# biosense_bgm220-pcbcart-cc-bma-flex-0521.net
KiCad netlist of a schematic drawn in EAGLE
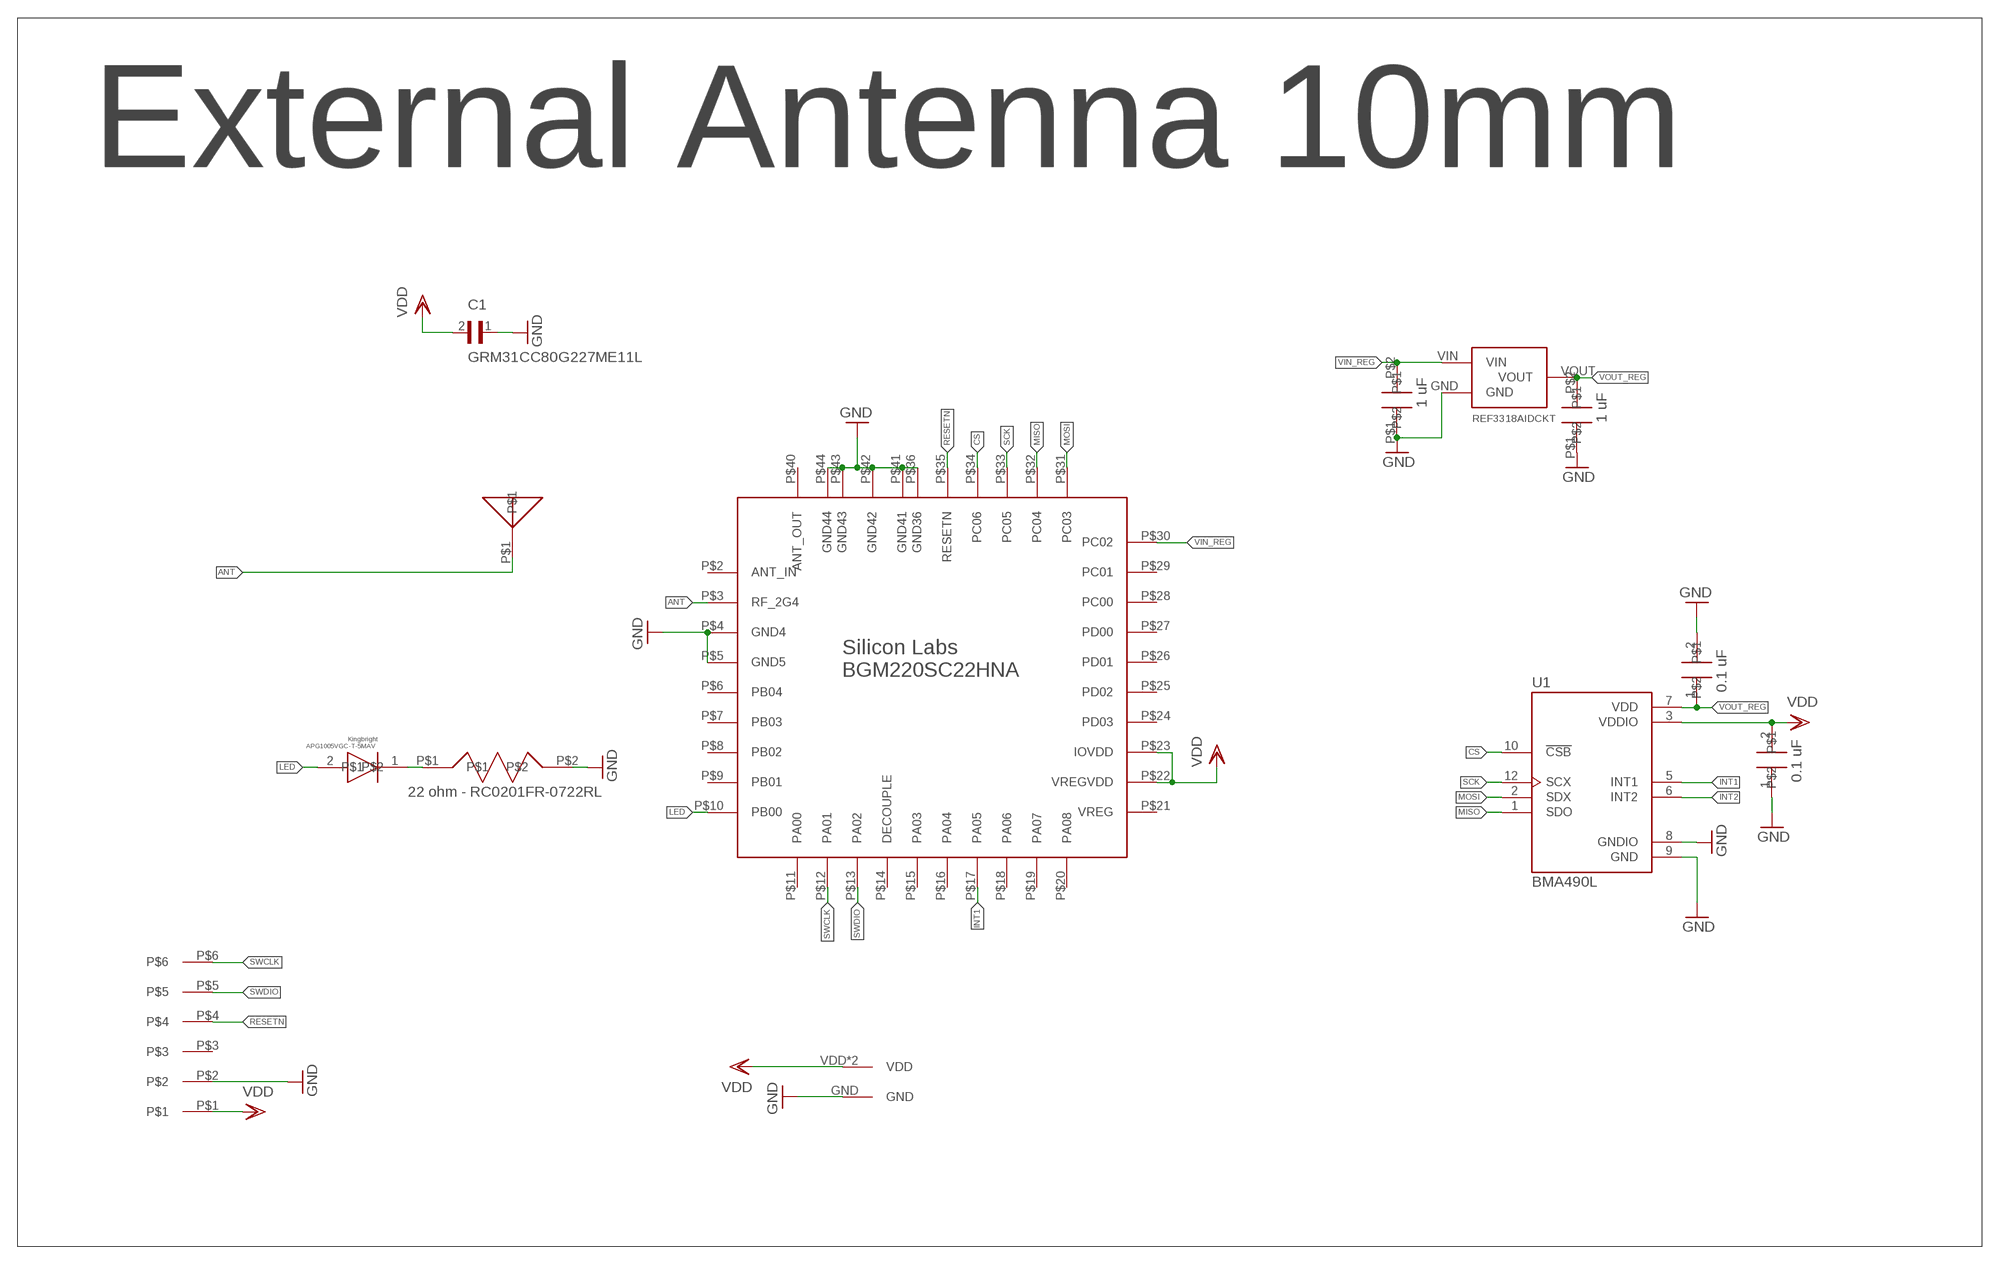
[diagram p0: schematic, sheet 1]

(export (version "E")
  (design (tool "Eeschema 10.0.6"))
  (components
    (comp (ref "C1")
      (value "GRM31CC80G227ME11L")
      (footprint "eagle-import:CAP3216X125N")
      (fields (field (name "DIGI-KEY_PART_NUMBER") "490-13250-1-ND") (field (name "MF") "Murata Electronics"))
      (libsource (lib "eagle-import") (part "GRM31CC80G227ME11L"))
    )
    (comp (ref "R1")
      (value "LEDRC0402N-L")
      (footprint "eagle-import:RC0402N-L")
      (fields (field (name "MANUFACTURER_PART_NUMBER") "CRCW04020000Z0ED"))
      (libsource (lib "eagle-import") (part "LEDRC0402N-L"))
    )
    (comp (ref "U$1")
      (value "BGM220SC22HNA")
      (footprint "eagle-import:BGM220SC22HNA")
      (libsource (lib "eagle-import") (part "BGM220SC22HNA"))
    )
    (comp (ref "U$2")
      (value "0U1_CAPACITOR")
      (footprint "eagle-import:FOOTPRINT_01005")
      (libsource (lib "eagle-import") (part "0U1_CAPACITOR"))
    )
    (comp (ref "U$3")
      (value "0U1_CAPACITOR")
      (footprint "eagle-import:FOOTPRINT_01005")
      (libsource (lib "eagle-import") (part "0U1_CAPACITOR"))
    )
    (comp (ref "U$4")
      (value "FPCHEADER")
      (footprint "eagle-import:FPCHEADER")
      (libsource (lib "eagle-import") (part "FPCHEADER"))
    )
    (comp (ref "U$5")
      (value "2450AT18A100")
      (footprint "eagle-import:2450AT18A100")
      (libsource (lib "eagle-import") (part "2450AT18A100"))
    )
    (comp (ref "U$6")
      (value "REF3318")
      (footprint "eagle-import:SOT-SC70")
      (libsource (lib "eagle-import") (part "REF3318"))
    )
    (comp (ref "U$7")
      (value "CR1025HOLDERCR1025_3")
      (footprint "eagle-import:CR1025_3")
      (libsource (lib "eagle-import") (part "CR1025HOLDERCR1025_3"))
    )
    (comp (ref "U$9")
      (value "1U_CAPACITOR")
      (footprint "eagle-import:FOOTPRINT_0201")
      (libsource (lib "eagle-import") (part "1U_CAPACITOR"))
    )
    (comp (ref "U$10")
      (value "1U_CAPACITOR")
      (footprint "eagle-import:FOOTPRINT_0201")
      (libsource (lib "eagle-import") (part "1U_CAPACITOR"))
    )
    (comp (ref "U$25")
      (value "22OHMRESISTOR")
      (footprint "eagle-import:FOOTPRINT_0201")
      (libsource (lib "eagle-import") (part "22OHMRESISTOR"))
    )
    (comp (ref "U1")
      (value "BMA490L")
      (footprint "eagle-import:BMA490L")
      (fields (field (name "MF") "Bosch Sensortec") (field (name "MP") "BMA400"))
      (libsource (lib "eagle-import") (part "BMA490L"))
    )
  )
  (nets
    (net (code "1") (name "ANT") (class "Default")
      (node (ref "U$1") (pin "P$3") (pinfunction "RF_2G4_P$3") (pintype "bidirectional"))
      (node (ref "U$5") (pin "P$1") (pinfunction "P$1_P$1") (pintype "bidirectional"))
    )
    (net (code "2") (name "CS") (class "Default")
      (node (ref "U$1") (pin "P$34") (pinfunction "PC06_P$34") (pintype "bidirectional"))
      (node (ref "U1") (pin "10") (pinfunction "~{CSB}_10") (pintype "input"))
    )
    (net (code "3") (name "GND") (class "Default")
      (node (ref "C1") (pin "1") (pinfunction "1_1") (pintype "passive"))
      (node (ref "U$1") (pin "P$36") (pinfunction "GND36_P$36") (pintype "bidirectional"))
      (node (ref "U$1") (pin "P$4") (pinfunction "GND4_P$4") (pintype "bidirectional"))
      (node (ref "U$1") (pin "P$41") (pinfunction "GND41_P$41") (pintype "bidirectional"))
      (node (ref "U$1") (pin "P$42") (pinfunction "GND42_P$42") (pintype "bidirectional"))
      (node (ref "U$1") (pin "P$43") (pinfunction "GND43_P$43") (pintype "bidirectional"))
      (node (ref "U$1") (pin "P$44") (pinfunction "GND44_P$44") (pintype "bidirectional"))
      (node (ref "U$1") (pin "P$5") (pinfunction "GND5_P$5") (pintype "bidirectional"))
      (node (ref "U$10") (pin "P$1") (pinfunction "P$1_P$1") (pintype "bidirectional"))
      (node (ref "U$2") (pin "1") (pinfunction "P$1_1") (pintype "bidirectional"))
      (node (ref "U$25") (pin "P$2") (pinfunction "P$2_P$2") (pintype "bidirectional"))
      (node (ref "U$3") (pin "2") (pinfunction "P$2_2") (pintype "bidirectional"))
      (node (ref "U$4") (pin "P$2") (pinfunction "P$2_P$2") (pintype "bidirectional"))
      (node (ref "U$6") (pin "GND") (pinfunction "GND_GND") (pintype "bidirectional"))
      (node (ref "U$7") (pin "GND") (pinfunction "GND_GND") (pintype "bidirectional"))
      (node (ref "U$9") (pin "P$1") (pinfunction "P$1_P$1") (pintype "bidirectional"))
      (node (ref "U1") (pin "8") (pinfunction "GNDIO_8") (pintype "power_in"))
      (node (ref "U1") (pin "9") (pinfunction "GND_9") (pintype "power_in"))
    )
    (net (code "4") (name "INT1") (class "Default")
      (node (ref "U$1") (pin "P$17") (pinfunction "PA05_P$17") (pintype "bidirectional"))
      (node (ref "U1") (pin "5") (pinfunction "INT1_5") (pintype "bidirectional"))
    )
    (net (code "5") (name "INT2") (class "Default")
      (node (ref "U1") (pin "6") (pinfunction "INT2_6") (pintype "bidirectional"))
    )
    (net (code "6") (name "LED") (class "Default")
      (node (ref "R1") (pin "2") (pinfunction "P$2_2") (pintype "bidirectional"))
      (node (ref "U$1") (pin "P$10") (pinfunction "PB00_P$10") (pintype "bidirectional"))
    )
    (net (code "7") (name "MISO") (class "Default")
      (node (ref "U$1") (pin "P$32") (pinfunction "PC04_P$32") (pintype "bidirectional"))
      (node (ref "U1") (pin "1") (pinfunction "SDO_1") (pintype "bidirectional"))
    )
    (net (code "8") (name "MOSI") (class "Default")
      (node (ref "U$1") (pin "P$31") (pinfunction "PC03_P$31") (pintype "bidirectional"))
      (node (ref "U1") (pin "2") (pinfunction "SDX_2") (pintype "bidirectional"))
    )
    (net (code "9") (name "Net-(R1-P$1)") (class "Default")
      (node (ref "R1") (pin "1") (pinfunction "P$1_1") (pintype "bidirectional"))
      (node (ref "U$25") (pin "P$1") (pinfunction "P$1_P$1") (pintype "bidirectional"))
    )
    (net (code "10") (name "RESETN") (class "Default")
      (node (ref "U$1") (pin "P$35") (pinfunction "RESETN_P$35") (pintype "bidirectional"))
      (node (ref "U$4") (pin "P$4") (pinfunction "P$4_P$4") (pintype "bidirectional"))
    )
    (net (code "11") (name "SCK") (class "Default")
      (node (ref "U$1") (pin "P$33") (pinfunction "PC05_P$33") (pintype "bidirectional"))
      (node (ref "U1") (pin "12") (pinfunction "SCX_12") (pintype "input"))
    )
    (net (code "12") (name "SWCLK") (class "Default")
      (node (ref "U$1") (pin "P$12") (pinfunction "PA01_P$12") (pintype "bidirectional"))
      (node (ref "U$4") (pin "P$6") (pinfunction "P$6_P$6") (pintype "bidirectional"))
    )
    (net (code "13") (name "SWDIO") (class "Default")
      (node (ref "U$1") (pin "P$13") (pinfunction "PA02_P$13") (pintype "bidirectional"))
      (node (ref "U$4") (pin "P$5") (pinfunction "P$5_P$5") (pintype "bidirectional"))
    )
    (net (code "14") (name "VDD") (class "Default")
      (node (ref "C1") (pin "2") (pinfunction "2_2") (pintype "passive"))
      (node (ref "U$1") (pin "P$22") (pinfunction "VREGVDD_P$22") (pintype "bidirectional"))
      (node (ref "U$1") (pin "P$23") (pinfunction "IOVDD_P$23") (pintype "bidirectional"))
      (node (ref "U$2") (pin "2") (pinfunction "P$2_2") (pintype "bidirectional"))
      (node (ref "U$4") (pin "P$1") (pinfunction "P$1_P$1") (pintype "bidirectional"))
      (node (ref "U$7") (pin "VDD") (pinfunction "VDD_VDD") (pintype "bidirectional"))
      (node (ref "U$7") (pin "VDD2") (pinfunction "VDD_VDD2") (pintype "bidirectional"))
      (node (ref "U1") (pin "3") (pinfunction "VDDIO_3") (pintype "power_in"))
    )
    (net (code "15") (name "VIN_REG") (class "Default")
      (node (ref "U$1") (pin "P$30") (pinfunction "PC02_P$30") (pintype "bidirectional"))
      (node (ref "U$6") (pin "VIN") (pinfunction "VIN_VIN") (pintype "bidirectional"))
      (node (ref "U$9") (pin "P$2") (pinfunction "P$2_P$2") (pintype "bidirectional"))
    )
    (net (code "16") (name "VOUT_REG") (class "Default")
      (node (ref "U$10") (pin "P$2") (pinfunction "P$2_P$2") (pintype "bidirectional"))
      (node (ref "U$3") (pin "1") (pinfunction "P$1_1") (pintype "bidirectional"))
      (node (ref "U$6") (pin "VOUT") (pinfunction "VOUT_VOUT") (pintype "bidirectional"))
      (node (ref "U1") (pin "7") (pinfunction "VDD_7") (pintype "power_in"))
    )
    (net (code "17") (name "unconnected-(U$1-ANT_IN-PadP$2)") (class "Default")
      (node (ref "U$1") (pin "P$2") (pinfunction "ANT_IN_P$2") (pintype "bidirectional"))
    )
    (net (code "18") (name "unconnected-(U$1-ANT_OUT-PadP$40)") (class "Default")
      (node (ref "U$1") (pin "P$40") (pinfunction "ANT_OUT_P$40") (pintype "bidirectional"))
    )
    (net (code "19") (name "unconnected-(U$1-DECOUPLE-PadP$14)") (class "Default")
      (node (ref "U$1") (pin "P$14") (pinfunction "DECOUPLE_P$14") (pintype "bidirectional"))
    )
    (net (code "20") (name "unconnected-(U$1-PA00-PadP$11)") (class "Default")
      (node (ref "U$1") (pin "P$11") (pinfunction "PA00_P$11") (pintype "bidirectional"))
    )
    (net (code "21") (name "unconnected-(U$1-PA03-PadP$15)") (class "Default")
      (node (ref "U$1") (pin "P$15") (pinfunction "PA03_P$15") (pintype "bidirectional"))
    )
    (net (code "22") (name "unconnected-(U$1-PA04-PadP$16)") (class "Default")
      (node (ref "U$1") (pin "P$16") (pinfunction "PA04_P$16") (pintype "bidirectional"))
    )
    (net (code "23") (name "unconnected-(U$1-PA06-PadP$18)") (class "Default")
      (node (ref "U$1") (pin "P$18") (pinfunction "PA06_P$18") (pintype "bidirectional"))
    )
    (net (code "24") (name "unconnected-(U$1-PA07-PadP$19)") (class "Default")
      (node (ref "U$1") (pin "P$19") (pinfunction "PA07_P$19") (pintype "bidirectional"))
    )
    (net (code "25") (name "unconnected-(U$1-PA08-PadP$20)") (class "Default")
      (node (ref "U$1") (pin "P$20") (pinfunction "PA08_P$20") (pintype "bidirectional"))
    )
    (net (code "26") (name "unconnected-(U$1-PB01-PadP$9)") (class "Default")
      (node (ref "U$1") (pin "P$9") (pinfunction "PB01_P$9") (pintype "bidirectional"))
    )
    (net (code "27") (name "unconnected-(U$1-PB02-PadP$8)") (class "Default")
      (node (ref "U$1") (pin "P$8") (pinfunction "PB02_P$8") (pintype "bidirectional"))
    )
    (net (code "28") (name "unconnected-(U$1-PB03-PadP$7)") (class "Default")
      (node (ref "U$1") (pin "P$7") (pinfunction "PB03_P$7") (pintype "bidirectional"))
    )
    (net (code "29") (name "unconnected-(U$1-PB04-PadP$6)") (class "Default")
      (node (ref "U$1") (pin "P$6") (pinfunction "PB04_P$6") (pintype "bidirectional"))
    )
    (net (code "30") (name "unconnected-(U$1-PC00-PadP$28)") (class "Default")
      (node (ref "U$1") (pin "P$28") (pinfunction "PC00_P$28") (pintype "bidirectional"))
    )
    (net (code "31") (name "unconnected-(U$1-PC01-PadP$29)") (class "Default")
      (node (ref "U$1") (pin "P$29") (pinfunction "PC01_P$29") (pintype "bidirectional"))
    )
    (net (code "32") (name "unconnected-(U$1-PD00-PadP$27)") (class "Default")
      (node (ref "U$1") (pin "P$27") (pinfunction "PD00_P$27") (pintype "bidirectional"))
    )
    (net (code "33") (name "unconnected-(U$1-PD01-PadP$26)") (class "Default")
      (node (ref "U$1") (pin "P$26") (pinfunction "PD01_P$26") (pintype "bidirectional"))
    )
    (net (code "34") (name "unconnected-(U$1-PD02-PadP$25)") (class "Default")
      (node (ref "U$1") (pin "P$25") (pinfunction "PD02_P$25") (pintype "bidirectional"))
    )
    (net (code "35") (name "unconnected-(U$1-PD03-PadP$24)") (class "Default")
      (node (ref "U$1") (pin "P$24") (pinfunction "PD03_P$24") (pintype "bidirectional"))
    )
    (net (code "36") (name "unconnected-(U$1-VREG-PadP$21)") (class "Default")
      (node (ref "U$1") (pin "P$21") (pinfunction "VREG_P$21") (pintype "bidirectional"))
    )
    (net (code "37") (name "unconnected-(U$4-PadP$3)") (class "Default")
      (node (ref "U$4") (pin "P$3") (pinfunction "P$3_P$3") (pintype "bidirectional"))
    )
  )
)
